# couch-reg-rc.net
KiCad netlist of a schematic drawn in EAGLE
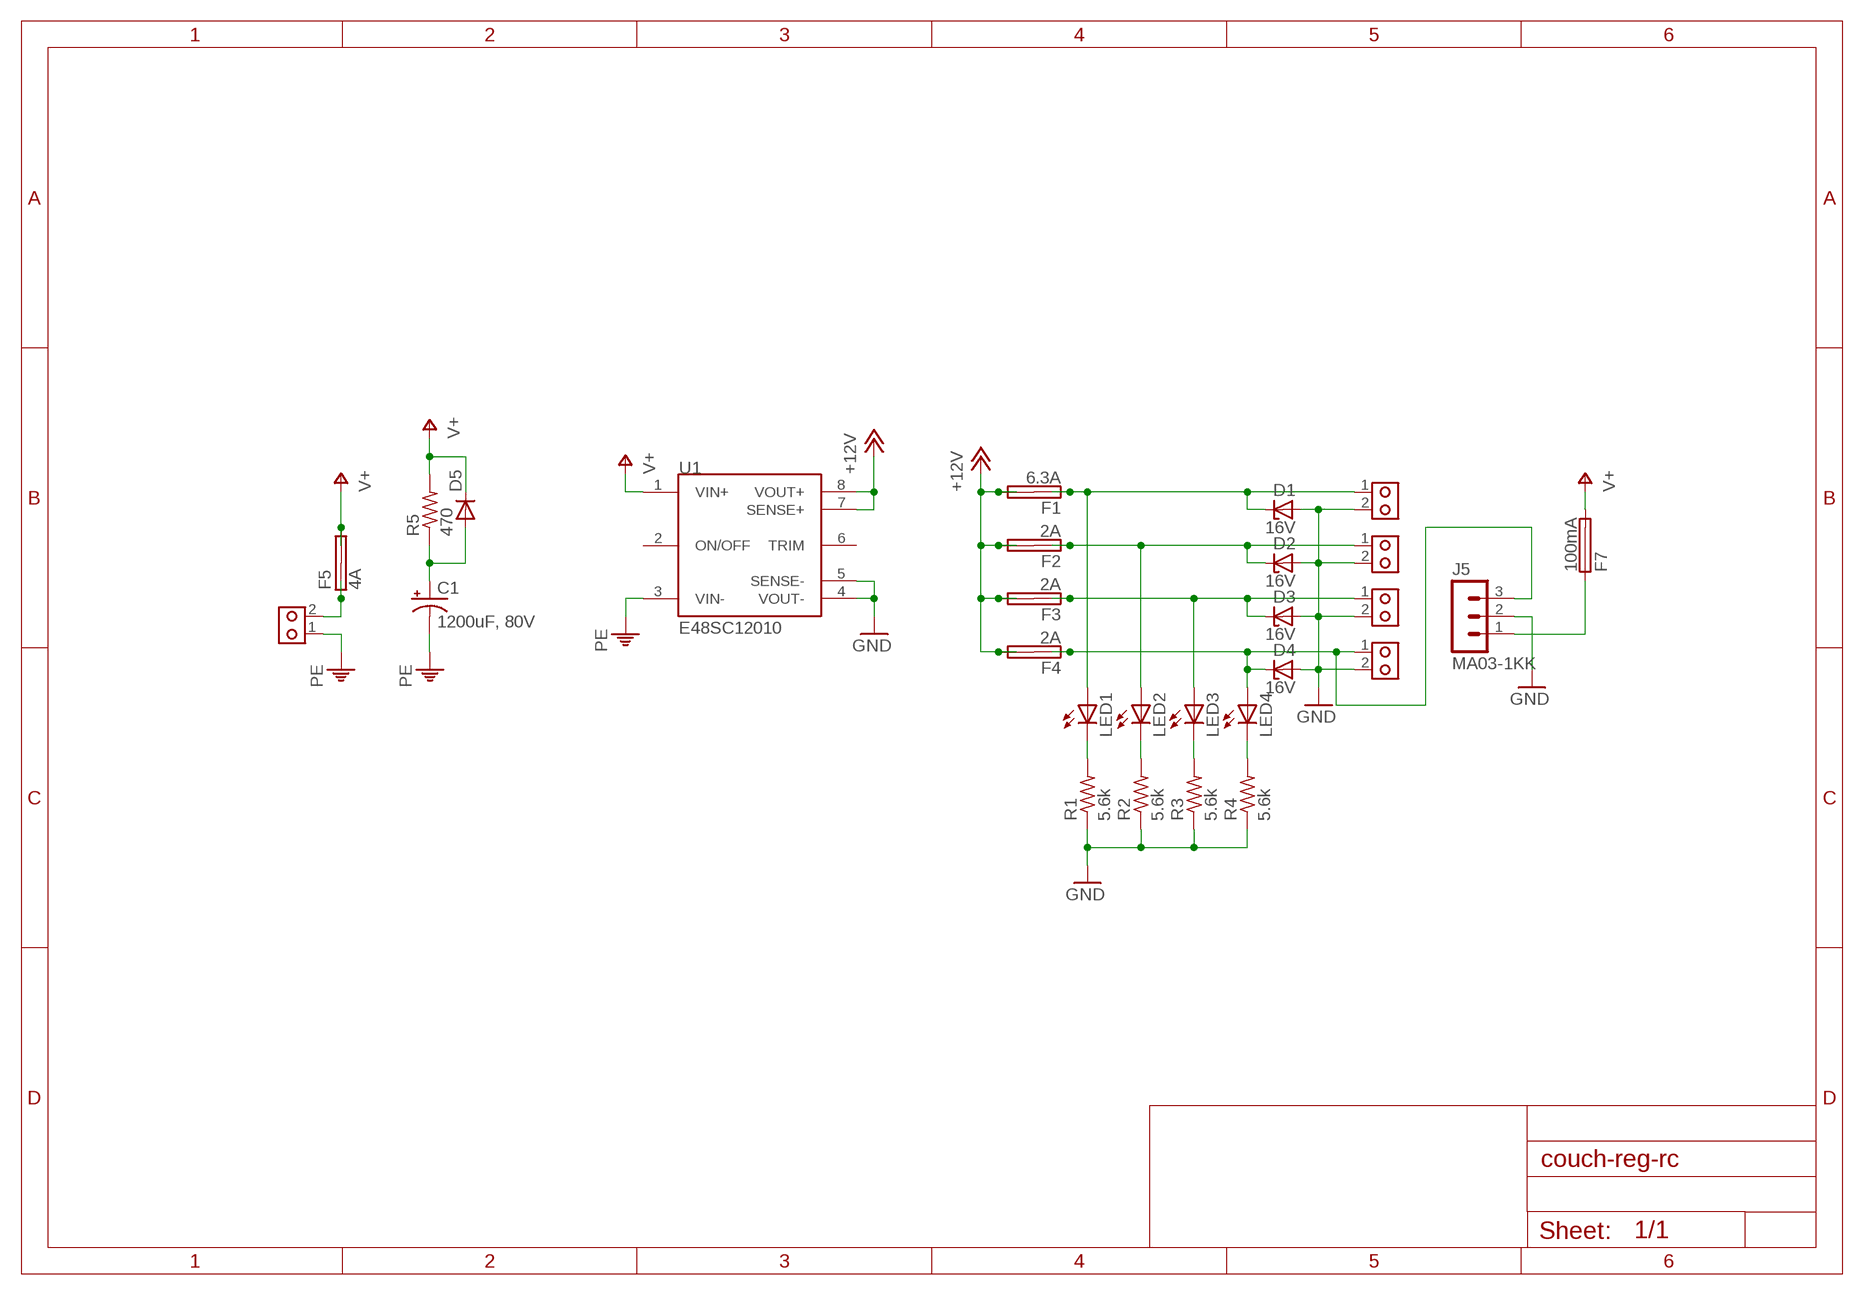
[diagram p0: schematic, sheet 1]

(export (version "E")
  (design (tool "Eeschema 10.0.6"))
  (components
    (comp (ref "C1")
      (value "1200uF, 80V")
      (footprint "eagle-import:E7,5-18")
      (libsource (lib "eagle-import") (part "CPOL-USE7.5-18"))
    )
    (comp (ref "D1")
      (value "16V")
      (footprint "eagle-import:C1702-15")
      (libsource (lib "eagle-import") (part "ZENER-DIODEC1702-15"))
    )
    (comp (ref "D2")
      (value "16V")
      (footprint "eagle-import:C1702-15")
      (libsource (lib "eagle-import") (part "ZENER-DIODEC1702-15"))
    )
    (comp (ref "D3")
      (value "16V")
      (footprint "eagle-import:C1702-15")
      (libsource (lib "eagle-import") (part "ZENER-DIODEC1702-15"))
    )
    (comp (ref "D4")
      (value "16V")
      (footprint "eagle-import:C1702-15")
      (libsource (lib "eagle-import") (part "ZENER-DIODEC1702-15"))
    )
    (comp (ref "D5")
      (value "DIODE-SMB")
      (footprint "eagle-import:SMB")
      (libsource (lib "eagle-import") (part "DIODE-SMB"))
    )
    (comp (ref "F1")
      (value "6.3A")
      (footprint "eagle-import:SHK20L")
      (libsource (lib "eagle-import") (part "SHK20L"))
    )
    (comp (ref "F2")
      (value "2A")
      (footprint "eagle-import:SHK20L")
      (libsource (lib "eagle-import") (part "SHK20L"))
    )
    (comp (ref "F3")
      (value "2A")
      (footprint "eagle-import:SHK20L")
      (libsource (lib "eagle-import") (part "SHK20L"))
    )
    (comp (ref "F4")
      (value "2A")
      (footprint "eagle-import:SHK20L")
      (libsource (lib "eagle-import") (part "SHK20L"))
    )
    (comp (ref "F5")
      (value "4A")
      (footprint "eagle-import:SHK20L")
      (libsource (lib "eagle-import") (part "SHK20L"))
    )
    (comp (ref "F7")
      (value "100mA")
      (footprint "eagle-import:0603")
      (libsource (lib "eagle-import") (part "FUSE0603"))
    )
    (comp (ref "J1")
      (value "PCBTERM2")
      (footprint "eagle-import:PCBTERM")
      (libsource (lib "eagle-import") (part "PCBTERM2"))
    )
    (comp (ref "J2")
      (value "PCBTERM2")
      (footprint "eagle-import:PCBTERM")
      (libsource (lib "eagle-import") (part "PCBTERM2"))
    )
    (comp (ref "J3")
      (value "PCBTERM2")
      (footprint "eagle-import:PCBTERM")
      (libsource (lib "eagle-import") (part "PCBTERM2"))
    )
    (comp (ref "J4")
      (value "PCBTERM2")
      (footprint "eagle-import:PCBTERM")
      (libsource (lib "eagle-import") (part "PCBTERM2"))
    )
    (comp (ref "J5")
      (value "MA03-1KK")
      (footprint "eagle-import:MOLEX-3")
      (libsource (lib "eagle-import") (part "MA03-1KK"))
    )
    (comp (ref "J6")
      (value "PCBTERM2")
      (footprint "eagle-import:PCBTERM")
      (libsource (lib "eagle-import") (part "PCBTERM2"))
    )
    (comp (ref "LED1")
      (value "LEDCHIPLED_0603")
      (footprint "eagle-import:CHIPLED_0603")
      (libsource (lib "eagle-import") (part "LEDCHIPLED_0603"))
    )
    (comp (ref "LED2")
      (value "LEDCHIPLED_0603")
      (footprint "eagle-import:CHIPLED_0603")
      (libsource (lib "eagle-import") (part "LEDCHIPLED_0603"))
    )
    (comp (ref "LED3")
      (value "LEDCHIPLED_0603")
      (footprint "eagle-import:CHIPLED_0603")
      (libsource (lib "eagle-import") (part "LEDCHIPLED_0603"))
    )
    (comp (ref "LED4")
      (value "LEDCHIPLED_0603")
      (footprint "eagle-import:CHIPLED_0603")
      (libsource (lib "eagle-import") (part "LEDCHIPLED_0603"))
    )
    (comp (ref "R1")
      (value "5.6k")
      (footprint "eagle-import:R0603")
      (libsource (lib "eagle-import") (part "R-US_R0603"))
    )
    (comp (ref "R2")
      (value "5.6k")
      (footprint "eagle-import:R0603")
      (libsource (lib "eagle-import") (part "R-US_R0603"))
    )
    (comp (ref "R3")
      (value "5.6k")
      (footprint "eagle-import:R0603")
      (libsource (lib "eagle-import") (part "R-US_R0603"))
    )
    (comp (ref "R4")
      (value "5.6k")
      (footprint "eagle-import:R0603")
      (libsource (lib "eagle-import") (part "R-US_R0603"))
    )
    (comp (ref "R5")
      (value "470")
      (footprint "eagle-import:R0603")
      (libsource (lib "eagle-import") (part "R-US_R0603"))
    )
    (comp (ref "U1")
      (value "E48SC12010")
      (footprint "eagle-import:E48SC12010")
      (libsource (lib "eagle-import") (part "E48SC12010"))
    )
  )
  (nets
    (net (code "1") (name "+12V") (class "Default")
      (node (ref "F1") (pin "2A") (pinfunction "2A_2A") (pintype "passive"))
      (node (ref "F1") (pin "2B") (pinfunction "2B_2B") (pintype "passive"))
      (node (ref "F2") (pin "2A") (pinfunction "2A_2A") (pintype "passive"))
      (node (ref "F2") (pin "2B") (pinfunction "2B_2B") (pintype "passive"))
      (node (ref "F3") (pin "2A") (pinfunction "2A_2A") (pintype "passive"))
      (node (ref "F3") (pin "2B") (pinfunction "2B_2B") (pintype "passive"))
      (node (ref "F4") (pin "2A") (pinfunction "2A_2A") (pintype "passive"))
      (node (ref "F4") (pin "2B") (pinfunction "2B_2B") (pintype "passive"))
      (node (ref "U1") (pin "7") (pinfunction "SENSE+_7") (pintype "input"))
      (node (ref "U1") (pin "8") (pinfunction "VOUT+_8") (pintype "power_in"))
    )
    (net (code "2") (name "GND") (class "Default")
      (node (ref "D1") (pin "A") (pinfunction "A_A") (pintype "passive"))
      (node (ref "D2") (pin "A") (pinfunction "A_A") (pintype "passive"))
      (node (ref "D3") (pin "A") (pinfunction "A_A") (pintype "passive"))
      (node (ref "D4") (pin "A") (pinfunction "A_A") (pintype "passive"))
      (node (ref "J1") (pin "2") (pinfunction "P$2_2") (pintype "passive"))
      (node (ref "J2") (pin "2") (pinfunction "P$2_2") (pintype "passive"))
      (node (ref "J3") (pin "2") (pinfunction "P$2_2") (pintype "passive"))
      (node (ref "J4") (pin "2") (pinfunction "P$2_2") (pintype "passive"))
      (node (ref "J5") (pin "2") (pinfunction "2_2") (pintype "passive"))
      (node (ref "R1") (pin "1") (pinfunction "1_1") (pintype "passive"))
      (node (ref "R2") (pin "1") (pinfunction "1_1") (pintype "passive"))
      (node (ref "R3") (pin "1") (pinfunction "1_1") (pintype "passive"))
      (node (ref "R4") (pin "1") (pinfunction "1_1") (pintype "passive"))
      (node (ref "U1") (pin "4") (pinfunction "VOUT-_4") (pintype "power_in"))
      (node (ref "U1") (pin "5") (pinfunction "SENSE-_5") (pintype "input"))
    )
    (net (code "3") (name "Net-(C1-Pad+)") (class "Default")
      (node (ref "C1") (pin "+") (pinfunction "+_+") (pintype "passive"))
      (node (ref "D5") (pin "A") (pinfunction "A_A") (pintype "passive"))
      (node (ref "R5") (pin "1") (pinfunction "1_1") (pintype "passive"))
    )
    (net (code "4") (name "Net-(F7-Pad1)") (class "Default")
      (node (ref "F7") (pin "1") (pinfunction "1_1") (pintype "passive"))
      (node (ref "J5") (pin "1") (pinfunction "1_1") (pintype "passive"))
    )
    (net (code "5") (name "Net-(J1-P$1)") (class "Default")
      (node (ref "D1") (pin "C") (pinfunction "C_C") (pintype "passive"))
      (node (ref "F1") (pin "1A") (pinfunction "1A_1A") (pintype "passive"))
      (node (ref "F1") (pin "1B") (pinfunction "1B_1B") (pintype "passive"))
      (node (ref "J1") (pin "1") (pinfunction "P$1_1") (pintype "passive"))
      (node (ref "LED1") (pin "A") (pinfunction "A_A") (pintype "passive"))
    )
    (net (code "6") (name "Net-(J2-P$1)") (class "Default")
      (node (ref "D2") (pin "C") (pinfunction "C_C") (pintype "passive"))
      (node (ref "F2") (pin "1A") (pinfunction "1A_1A") (pintype "passive"))
      (node (ref "F2") (pin "1B") (pinfunction "1B_1B") (pintype "passive"))
      (node (ref "J2") (pin "1") (pinfunction "P$1_1") (pintype "passive"))
      (node (ref "LED2") (pin "A") (pinfunction "A_A") (pintype "passive"))
    )
    (net (code "7") (name "Net-(J3-P$1)") (class "Default")
      (node (ref "D3") (pin "C") (pinfunction "C_C") (pintype "passive"))
      (node (ref "F3") (pin "1A") (pinfunction "1A_1A") (pintype "passive"))
      (node (ref "F3") (pin "1B") (pinfunction "1B_1B") (pintype "passive"))
      (node (ref "J3") (pin "1") (pinfunction "P$1_1") (pintype "passive"))
      (node (ref "LED3") (pin "A") (pinfunction "A_A") (pintype "passive"))
    )
    (net (code "8") (name "Net-(J4-P$1)") (class "Default")
      (node (ref "D4") (pin "C") (pinfunction "C_C") (pintype "passive"))
      (node (ref "F4") (pin "1A") (pinfunction "1A_1A") (pintype "passive"))
      (node (ref "F4") (pin "1B") (pinfunction "1B_1B") (pintype "passive"))
      (node (ref "J4") (pin "1") (pinfunction "P$1_1") (pintype "passive"))
      (node (ref "J5") (pin "3") (pinfunction "3_3") (pintype "passive"))
      (node (ref "LED4") (pin "A") (pinfunction "A_A") (pintype "passive"))
    )
    (net (code "9") (name "Net-(J6-P$2)") (class "Default")
      (node (ref "F5") (pin "1A") (pinfunction "1A_1A") (pintype "passive"))
      (node (ref "F5") (pin "1B") (pinfunction "1B_1B") (pintype "passive"))
      (node (ref "J6") (pin "2") (pinfunction "P$2_2") (pintype "passive"))
    )
    (net (code "10") (name "Net-(LED1-PadC)") (class "Default")
      (node (ref "LED1") (pin "C") (pinfunction "C_C") (pintype "passive"))
      (node (ref "R1") (pin "2") (pinfunction "2_2") (pintype "passive"))
    )
    (net (code "11") (name "Net-(LED2-PadC)") (class "Default")
      (node (ref "LED2") (pin "C") (pinfunction "C_C") (pintype "passive"))
      (node (ref "R2") (pin "2") (pinfunction "2_2") (pintype "passive"))
    )
    (net (code "12") (name "Net-(LED3-PadC)") (class "Default")
      (node (ref "LED3") (pin "C") (pinfunction "C_C") (pintype "passive"))
      (node (ref "R3") (pin "2") (pinfunction "2_2") (pintype "passive"))
    )
    (net (code "13") (name "Net-(LED4-PadC)") (class "Default")
      (node (ref "LED4") (pin "C") (pinfunction "C_C") (pintype "passive"))
      (node (ref "R4") (pin "2") (pinfunction "2_2") (pintype "passive"))
    )
    (net (code "14") (name "PE") (class "Default")
      (node (ref "C1") (pin "-") (pinfunction "-_-") (pintype "passive"))
      (node (ref "J6") (pin "1") (pinfunction "P$1_1") (pintype "passive"))
      (node (ref "U1") (pin "3") (pinfunction "VIN-_3") (pintype "power_in"))
    )
    (net (code "15") (name "V+") (class "Default")
      (node (ref "D5") (pin "C") (pinfunction "C_C") (pintype "passive"))
      (node (ref "F5") (pin "2A") (pinfunction "2A_2A") (pintype "passive"))
      (node (ref "F5") (pin "2B") (pinfunction "2B_2B") (pintype "passive"))
      (node (ref "F7") (pin "2") (pinfunction "2_2") (pintype "passive"))
      (node (ref "R5") (pin "2") (pinfunction "2_2") (pintype "passive"))
      (node (ref "U1") (pin "1") (pinfunction "VIN+_1") (pintype "power_in"))
    )
    (net (code "16") (name "unconnected-(U1-ON{slash}OFF-Pad2)") (class "Default")
      (node (ref "U1") (pin "2") (pinfunction "ON/OFF_2") (pintype "input"))
    )
    (net (code "17") (name "unconnected-(U1-TRIM-Pad6)") (class "Default")
      (node (ref "U1") (pin "6") (pinfunction "TRIM_6") (pintype "input"))
    )
  )
)
